# TDA5340_1.net
KiCad netlist of a schematic drawn in Altium Designer
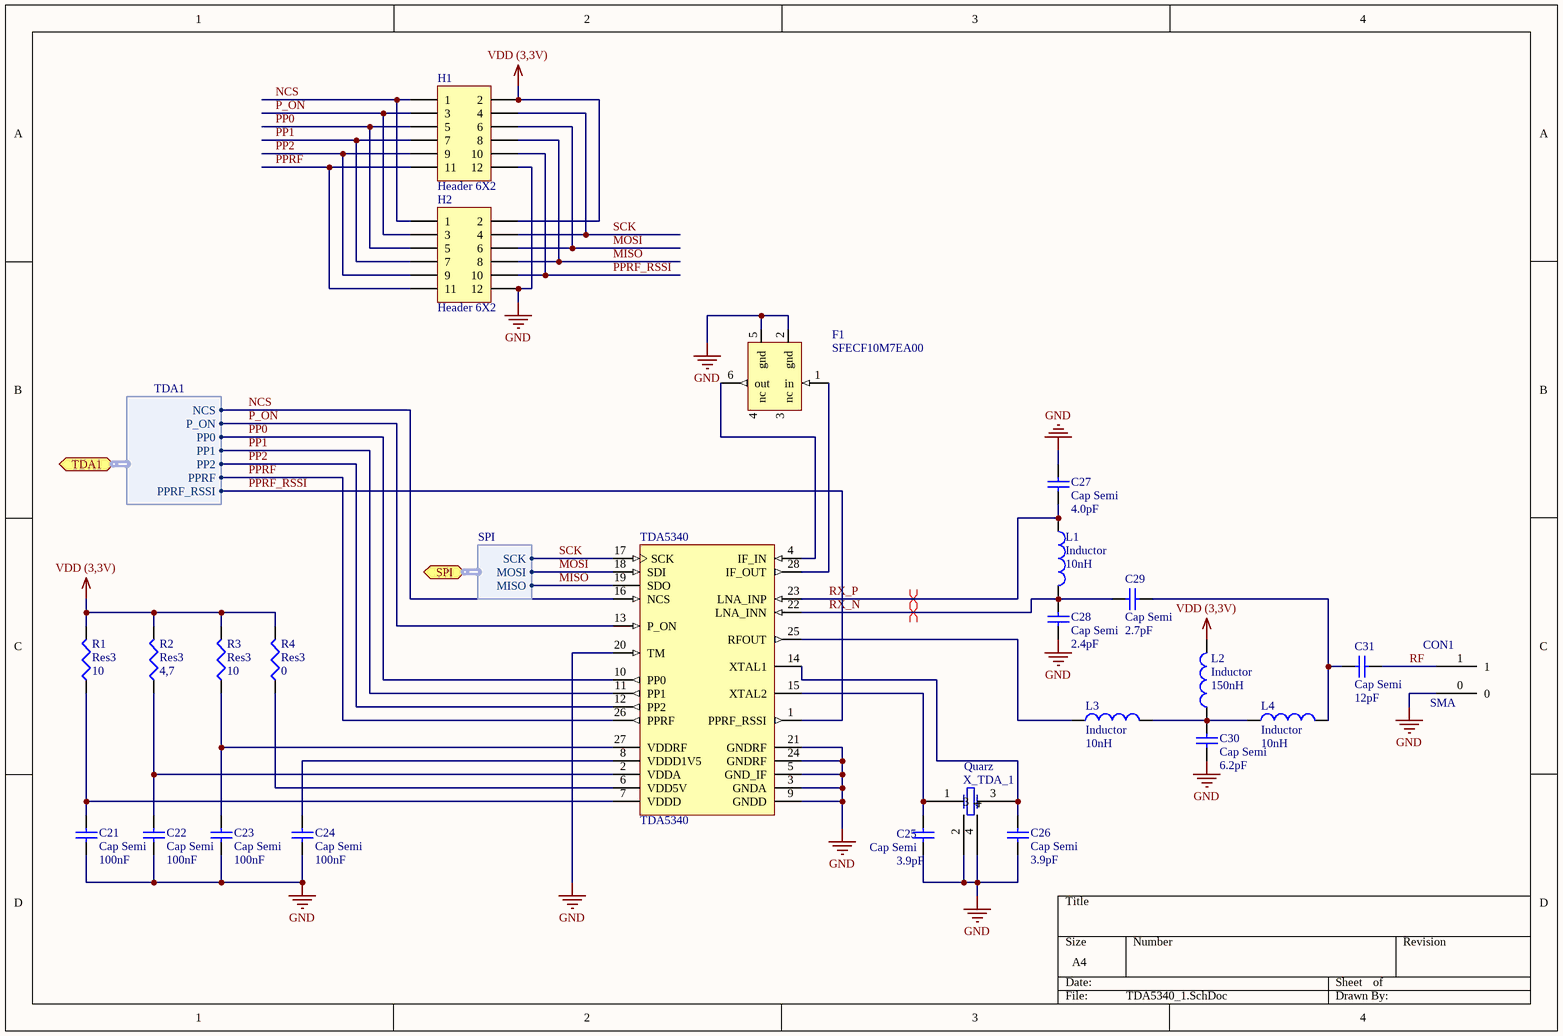
[diagram p0: TDA5340_1.SchDoc]

(export (version "E")
  (design (tool "Eeschema 10.0.6"))
  (components
    (comp (ref "C21")
      (value "Cap Semi")
      (footprint "0402")
      (description "Capacitor (Semiconductor SIM Model)")
      (fields (field (name "ALTIUM_VALUE") "100nF") (field (name "PUBLISHER") "Altium Limited"))
      (libsource (lib "Miscellaneous Devices") (part "Cap Semi"))
    )
    (comp (ref "C22")
      (value "Cap Semi")
      (footprint "0402")
      (description "Capacitor (Semiconductor SIM Model)")
      (fields (field (name "ALTIUM_VALUE") "100nF") (field (name "PUBLISHER") "Altium Limited"))
      (libsource (lib "Miscellaneous Devices") (part "Cap Semi"))
    )
    (comp (ref "C23")
      (value "Cap Semi")
      (footprint "0402")
      (description "Capacitor (Semiconductor SIM Model)")
      (fields (field (name "ALTIUM_VALUE") "100nF") (field (name "PUBLISHER") "Altium Limited"))
      (libsource (lib "Miscellaneous Devices") (part "Cap Semi"))
    )
    (comp (ref "C24")
      (value "Cap Semi")
      (footprint "0402")
      (description "Capacitor (Semiconductor SIM Model)")
      (fields (field (name "ALTIUM_VALUE") "100nF") (field (name "PUBLISHER") "Altium Limited"))
      (libsource (lib "Miscellaneous Devices") (part "Cap Semi"))
    )
    (comp (ref "C25")
      (value "Cap Semi")
      (footprint "0402")
      (description "Capacitor (Semiconductor SIM Model)")
      (fields (field (name "ALTIUM_VALUE") "3.9pF") (field (name "PUBLISHER") "Altium Limited"))
      (libsource (lib "Miscellaneous Devices") (part "Cap Semi"))
    )
    (comp (ref "C26")
      (value "Cap Semi")
      (footprint "0402")
      (description "Capacitor (Semiconductor SIM Model)")
      (fields (field (name "ALTIUM_VALUE") "3.9pF") (field (name "PUBLISHER") "Altium Limited"))
      (libsource (lib "Miscellaneous Devices") (part "Cap Semi"))
    )
    (comp (ref "C27")
      (value "Cap Semi")
      (footprint "0402")
      (description "Capacitor (Semiconductor SIM Model)")
      (fields (field (name "ALTIUM_VALUE") "4.0pF") (field (name "PUBLISHER") "Altium Limited"))
      (libsource (lib "Miscellaneous Devices") (part "Cap Semi"))
    )
    (comp (ref "C28")
      (value "Cap Semi")
      (footprint "0402")
      (description "Capacitor (Semiconductor SIM Model)")
      (fields (field (name "ALTIUM_VALUE") "2.4pF") (field (name "PUBLISHER") "Altium Limited"))
      (libsource (lib "Miscellaneous Devices") (part "Cap Semi"))
    )
    (comp (ref "C29")
      (value "Cap Semi")
      (footprint "0402")
      (description "Capacitor (Semiconductor SIM Model)")
      (fields (field (name "ALTIUM_VALUE") "2.7pF") (field (name "PUBLISHER") "Altium Limited"))
      (libsource (lib "Miscellaneous Devices") (part "Cap Semi"))
    )
    (comp (ref "C30")
      (value "Cap Semi")
      (footprint "0402")
      (description "Capacitor (Semiconductor SIM Model)")
      (fields (field (name "ALTIUM_VALUE") "6.2pF") (field (name "PUBLISHER") "Altium Limited"))
      (libsource (lib "Miscellaneous Devices") (part "Cap Semi"))
    )
    (comp (ref "C31")
      (value "Cap Semi")
      (footprint "0402")
      (description "Capacitor (Semiconductor SIM Model)")
      (fields (field (name "ALTIUM_VALUE") "12pF") (field (name "PUBLISHER") "Altium Limited"))
      (libsource (lib "Miscellaneous Devices") (part "Cap Semi"))
    )
    (comp (ref "CON1") (value "SMA") (footprint "SMA") (libsource (lib "Schlib1_rev2") (part "SMA")))
    (comp (ref "F1")
      (value "SFECF10M7EA00")
      (footprint "SOP6")
      (libsource (lib "Schlib1") (part "SFECF10M7EA00"))
    )
    (comp (ref "H1")
      (value "Header 6X2")
      (footprint "HDR2X6")
      (description "Header, 6-Pin, Dual row")
      (fields (field (name "PUBLISHER") "Altium Limited"))
      (libsource (lib "Miscellaneous Connectors") (part "Header 6X2"))
    )
    (comp (ref "H2")
      (value "Header 6X2")
      (footprint "HDR2X6")
      (description "Header, 6-Pin, Dual row")
      (fields (field (name "PUBLISHER") "Altium Limited"))
      (libsource (lib "Miscellaneous Connectors") (part "Header 6X2"))
    )
    (comp (ref "L1")
      (value "Inductor")
      (footprint "0603")
      (fields (field (name "ALTIUM_VALUE") "10nH") (field (name "PUBLISHER") "Altium Limited"))
      (libsource (lib "Miscellaneous Devices") (part "Inductor"))
    )
    (comp (ref "L2")
      (value "Inductor")
      (footprint "0603")
      (fields (field (name "ALTIUM_VALUE") "150nH") (field (name "PUBLISHER") "Altium Limited"))
      (libsource (lib "Miscellaneous Devices") (part "Inductor"))
    )
    (comp (ref "L3")
      (value "Inductor")
      (footprint "0603")
      (fields (field (name "ALTIUM_VALUE") "10nH") (field (name "PUBLISHER") "Altium Limited"))
      (libsource (lib "Miscellaneous Devices") (part "Inductor"))
    )
    (comp (ref "L4")
      (value "Inductor")
      (footprint "0603")
      (fields (field (name "ALTIUM_VALUE") "10nH") (field (name "PUBLISHER") "Altium Limited"))
      (libsource (lib "Miscellaneous Devices") (part "Inductor"))
    )
    (comp (ref "R1")
      (value "Res3")
      (footprint "J1-0603")
      (description "Resistor")
      (fields (field (name "ALTIUM_VALUE") "10") (field (name "PUBLISHER") "Altium Limited"))
      (libsource (lib "Miscellaneous Devices") (part "Res3"))
    )
    (comp (ref "R2")
      (value "Res3")
      (footprint "J1-0603")
      (description "Resistor")
      (fields (field (name "ALTIUM_VALUE") "4,7") (field (name "PUBLISHER") "Altium Limited"))
      (libsource (lib "Miscellaneous Devices") (part "Res3"))
    )
    (comp (ref "R3")
      (value "Res3")
      (footprint "J1-0603")
      (description "Resistor")
      (fields (field (name "ALTIUM_VALUE") "10") (field (name "PUBLISHER") "Altium Limited"))
      (libsource (lib "Miscellaneous Devices") (part "Res3"))
    )
    (comp (ref "R4")
      (value "Res3")
      (footprint "J1-0603")
      (description "Resistor")
      (fields (field (name "ALTIUM_VALUE") "0") (field (name "PUBLISHER") "Altium Limited"))
      (libsource (lib "Miscellaneous Devices") (part "Res3"))
    )
    (comp (ref "TDA5340")
      (value "TDA5340")
      (footprint "INF-PG-TSSOP-28_N")
      (description "High Sensitivity Multi-Channel Transceiver, -40 to 110 degC, PG-TSSOP-28, Green")
      (fields (field (name "MANUFACTURER") "Infineon"))
      (libsource (lib "TDA5340") (part "TDA5340"))
    )
    (comp (ref "X_TDA_1") (value "Quarz") (footprint "Quarz") (libsource (lib "Schlib1") (part "Quarz")))
  )
  (nets
    (net (code "3") (name "/MISO") (class "Default")
      (node (ref "H1") (pin "8") (pinfunction "8_8") (pintype "passive"))
      (node (ref "H2") (pin "8") (pinfunction "8_8") (pintype "passive"))
      (node (ref "TDA5340") (pin "19") (pinfunction "SDO_19") (pintype "tri_state"))
    )
    (net (code "4") (name "/MOSI") (class "Default")
      (node (ref "H1") (pin "6") (pinfunction "6_6") (pintype "passive"))
      (node (ref "H2") (pin "6") (pinfunction "6_6") (pintype "passive"))
      (node (ref "TDA5340") (pin "18") (pinfunction "SDI_18") (pintype "input"))
    )
    (net (code "5") (name "/NCS") (class "Default")
      (node (ref "H1") (pin "1") (pinfunction "1_1") (pintype "passive"))
      (node (ref "H2") (pin "1") (pinfunction "1_1") (pintype "passive"))
      (node (ref "TDA5340") (pin "16") (pinfunction "NCS_16") (pintype "input"))
    )
    (net (code "6") (name "/PP0") (class "Default")
      (node (ref "H1") (pin "5") (pinfunction "5_5") (pintype "passive"))
      (node (ref "H2") (pin "5") (pinfunction "5_5") (pintype "passive"))
      (node (ref "TDA5340") (pin "10") (pinfunction "PP0_10") (pintype "output"))
    )
    (net (code "7") (name "/PP1") (class "Default")
      (node (ref "H1") (pin "7") (pinfunction "7_7") (pintype "passive"))
      (node (ref "H2") (pin "7") (pinfunction "7_7") (pintype "passive"))
      (node (ref "TDA5340") (pin "11") (pinfunction "PP1_11") (pintype "output"))
    )
    (net (code "8") (name "/PP2") (class "Default")
      (node (ref "H1") (pin "9") (pinfunction "9_9") (pintype "passive"))
      (node (ref "H2") (pin "9") (pinfunction "9_9") (pintype "passive"))
      (node (ref "TDA5340") (pin "12") (pinfunction "PP2_12") (pintype "output"))
    )
    (net (code "9") (name "/PPRF") (class "Default")
      (node (ref "H1") (pin "11") (pinfunction "11_11") (pintype "passive"))
      (node (ref "H2") (pin "11") (pinfunction "11_11") (pintype "passive"))
      (node (ref "TDA5340") (pin "26") (pinfunction "PPRF_26") (pintype "output"))
    )
    (net (code "10") (name "/PPRF_RSSI") (class "Default")
      (node (ref "H1") (pin "10") (pinfunction "10_10") (pintype "passive"))
      (node (ref "H2") (pin "10") (pinfunction "10_10") (pintype "passive"))
      (node (ref "TDA5340") (pin "1") (pinfunction "PPRF_RSSI_1") (pintype "output"))
    )
    (net (code "11") (name "/P_ON") (class "Default")
      (node (ref "H1") (pin "3") (pinfunction "3_3") (pintype "passive"))
      (node (ref "H2") (pin "3") (pinfunction "3_3") (pintype "passive"))
      (node (ref "TDA5340") (pin "13") (pinfunction "P_ON_13") (pintype "input"))
    )
    (net (code "12") (name "/RF") (class "Default")
      (node (ref "C31") (pin "2") (pinfunction "2_2") (pintype "passive"))
      (node (ref "CON1") (pin "1") (pinfunction "1_1") (pintype "passive"))
    )
    (net (code "13") (name "/RX_N") (class "Default")
      (node (ref "C28") (pin "1") (pinfunction "1_1") (pintype "passive"))
      (node (ref "C29") (pin "2") (pinfunction "2_2") (pintype "passive"))
      (node (ref "L1") (pin "2") (pinfunction "2_2") (pintype "passive"))
      (node (ref "TDA5340") (pin "22") (pinfunction "LNA_INN_22") (pintype "input"))
    )
    (net (code "14") (name "/RX_P") (class "Default")
      (node (ref "C27") (pin "2") (pinfunction "2_2") (pintype "passive"))
      (node (ref "L1") (pin "1") (pinfunction "1_1") (pintype "passive"))
      (node (ref "TDA5340") (pin "23") (pinfunction "LNA_INP_23") (pintype "input"))
    )
    (net (code "15") (name "/SCK") (class "Default")
      (node (ref "H1") (pin "4") (pinfunction "4_4") (pintype "passive"))
      (node (ref "H2") (pin "4") (pinfunction "4_4") (pintype "passive"))
      (node (ref "TDA5340") (pin "17") (pinfunction "SCK_17") (pintype "input"))
    )
    (net (code "18") (name "GND") (class "Default")
      (node (ref "C21") (pin "2") (pinfunction "2_2") (pintype "passive"))
      (node (ref "C22") (pin "2") (pinfunction "2_2") (pintype "passive"))
      (node (ref "C23") (pin "2") (pinfunction "2_2") (pintype "passive"))
      (node (ref "C24") (pin "2") (pinfunction "2_2") (pintype "passive"))
      (node (ref "C25") (pin "2") (pinfunction "2_2") (pintype "passive"))
      (node (ref "C26") (pin "1") (pinfunction "1_1") (pintype "passive"))
      (node (ref "C27") (pin "1") (pinfunction "1_1") (pintype "passive"))
      (node (ref "C28") (pin "2") (pinfunction "2_2") (pintype "passive"))
      (node (ref "C30") (pin "1") (pinfunction "1_1") (pintype "passive"))
      (node (ref "CON1") (pin "0") (pinfunction "0_0") (pintype "passive"))
      (node (ref "F1") (pin "2") (pinfunction "gnd_2") (pintype "power_in"))
      (node (ref "F1") (pin "5") (pinfunction "gnd_5") (pintype "passive"))
      (node (ref "H1") (pin "12") (pinfunction "12_12") (pintype "passive"))
      (node (ref "H2") (pin "12") (pinfunction "12_12") (pintype "passive"))
      (node (ref "TDA5340") (pin "20") (pinfunction "TM_20") (pintype "input"))
      (node (ref "TDA5340") (pin "21") (pinfunction "GNDRF_21") (pintype "power_in"))
      (node (ref "TDA5340") (pin "24") (pinfunction "GNDRF_24") (pintype "power_in"))
      (node (ref "TDA5340") (pin "3") (pinfunction "GNDA_3") (pintype "power_in"))
      (node (ref "TDA5340") (pin "5") (pinfunction "GND_IF_5") (pintype "power_in"))
      (node (ref "TDA5340") (pin "9") (pinfunction "GNDD_9") (pintype "power_in"))
      (node (ref "X_TDA_1") (pin "2") (pinfunction "2_2") (pintype "passive"))
      (node (ref "X_TDA_1") (pin "4") (pinfunction "4_4") (pintype "passive"))
    )
    (net (code "19") (name "Net-(C29-Pad1)") (class "Default")
      (node (ref "C29") (pin "1") (pinfunction "1_1") (pintype "passive"))
      (node (ref "C31") (pin "1") (pinfunction "1_1") (pintype "passive"))
      (node (ref "L4") (pin "2") (pinfunction "2_2") (pintype "passive"))
    )
    (net (code "20") (name "Net-(C30-Pad2)") (class "Default")
      (node (ref "C30") (pin "2") (pinfunction "2_2") (pintype "passive"))
      (node (ref "L2") (pin "1") (pinfunction "1_1") (pintype "passive"))
      (node (ref "L3") (pin "2") (pinfunction "2_2") (pintype "passive"))
      (node (ref "L4") (pin "1") (pinfunction "1_1") (pintype "passive"))
    )
    (net (code "21") (name "Net-(F1-in)") (class "Default")
      (node (ref "F1") (pin "1") (pinfunction "in_1") (pintype "input"))
      (node (ref "TDA5340") (pin "28") (pinfunction "IF_OUT_28") (pintype "output"))
    )
    (net (code "22") (name "Net-(F1-out)") (class "Default")
      (node (ref "F1") (pin "6") (pinfunction "out_6") (pintype "output"))
      (node (ref "TDA5340") (pin "4") (pinfunction "IF_IN_4") (pintype "input"))
    )
    (net (code "23") (name "Net-(TDA5340-RFOUT)") (class "Default")
      (node (ref "L3") (pin "1") (pinfunction "1_1") (pintype "passive"))
      (node (ref "TDA5340") (pin "25") (pinfunction "RFOUT_25") (pintype "output"))
    )
    (net (code "24") (name "Net-(TDA5340-VDD5V)") (class "Default")
      (node (ref "R4") (pin "1") (pinfunction "1_1") (pintype "passive"))
      (node (ref "TDA5340") (pin "6") (pinfunction "VDD5V_6") (pintype "power_in"))
    )
    (net (code "25") (name "Net-(TDA5340-VDDA)") (class "Default")
      (node (ref "C22") (pin "1") (pinfunction "1_1") (pintype "passive"))
      (node (ref "R2") (pin "1") (pinfunction "1_1") (pintype "passive"))
      (node (ref "TDA5340") (pin "2") (pinfunction "VDDA_2") (pintype "power_in"))
    )
    (net (code "26") (name "Net-(TDA5340-VDDD)") (class "Default")
      (node (ref "C21") (pin "1") (pinfunction "1_1") (pintype "passive"))
      (node (ref "R1") (pin "1") (pinfunction "1_1") (pintype "passive"))
      (node (ref "TDA5340") (pin "7") (pinfunction "VDDD_7") (pintype "power_in"))
    )
    (net (code "27") (name "Net-(TDA5340-VDDD1V5)") (class "Default")
      (node (ref "C24") (pin "1") (pinfunction "1_1") (pintype "passive"))
      (node (ref "TDA5340") (pin "8") (pinfunction "VDDD1V5_8") (pintype "power_in"))
    )
    (net (code "28") (name "Net-(TDA5340-VDDRF)") (class "Default")
      (node (ref "C23") (pin "1") (pinfunction "1_1") (pintype "passive"))
      (node (ref "R3") (pin "1") (pinfunction "1_1") (pintype "passive"))
      (node (ref "TDA5340") (pin "27") (pinfunction "VDDRF_27") (pintype "power_in"))
    )
    (net (code "29") (name "Net-(TDA5340-XTAL1)") (class "Default")
      (node (ref "C26") (pin "2") (pinfunction "2_2") (pintype "passive"))
      (node (ref "TDA5340") (pin "14") (pinfunction "XTAL1_14") (pintype "passive"))
      (node (ref "X_TDA_1") (pin "3") (pinfunction "3_3") (pintype "passive"))
    )
    (net (code "30") (name "Net-(TDA5340-XTAL2)") (class "Default")
      (node (ref "C25") (pin "1") (pinfunction "1_1") (pintype "passive"))
      (node (ref "TDA5340") (pin "15") (pinfunction "XTAL2_15") (pintype "passive"))
      (node (ref "X_TDA_1") (pin "1") (pinfunction "1_1") (pintype "passive"))
    )
    (net (code "31") (name "VDD (3,3V)") (class "Default")
      (node (ref "H1") (pin "2") (pinfunction "2_2") (pintype "passive"))
      (node (ref "H2") (pin "2") (pinfunction "2_2") (pintype "passive"))
      (node (ref "L2") (pin "2") (pinfunction "2_2") (pintype "passive"))
      (node (ref "R1") (pin "2") (pinfunction "2_2") (pintype "passive"))
      (node (ref "R2") (pin "2") (pinfunction "2_2") (pintype "passive"))
      (node (ref "R3") (pin "2") (pinfunction "2_2") (pintype "passive"))
      (node (ref "R4") (pin "2") (pinfunction "2_2") (pintype "passive"))
    )
    (net (code "32") (name "unconnected-(F1-nc-Pad3)") (class "Default")
      (node (ref "F1") (pin "3") (pinfunction "nc_3") (pintype "passive"))
    )
    (net (code "33") (name "unconnected-(F1-nc-Pad4)") (class "Default")
      (node (ref "F1") (pin "4") (pinfunction "nc_4") (pintype "passive"))
    )
  )
)
